# ESP32_Dev_Board.net
KiCad netlist of a schematic drawn in EasyEDA Pro
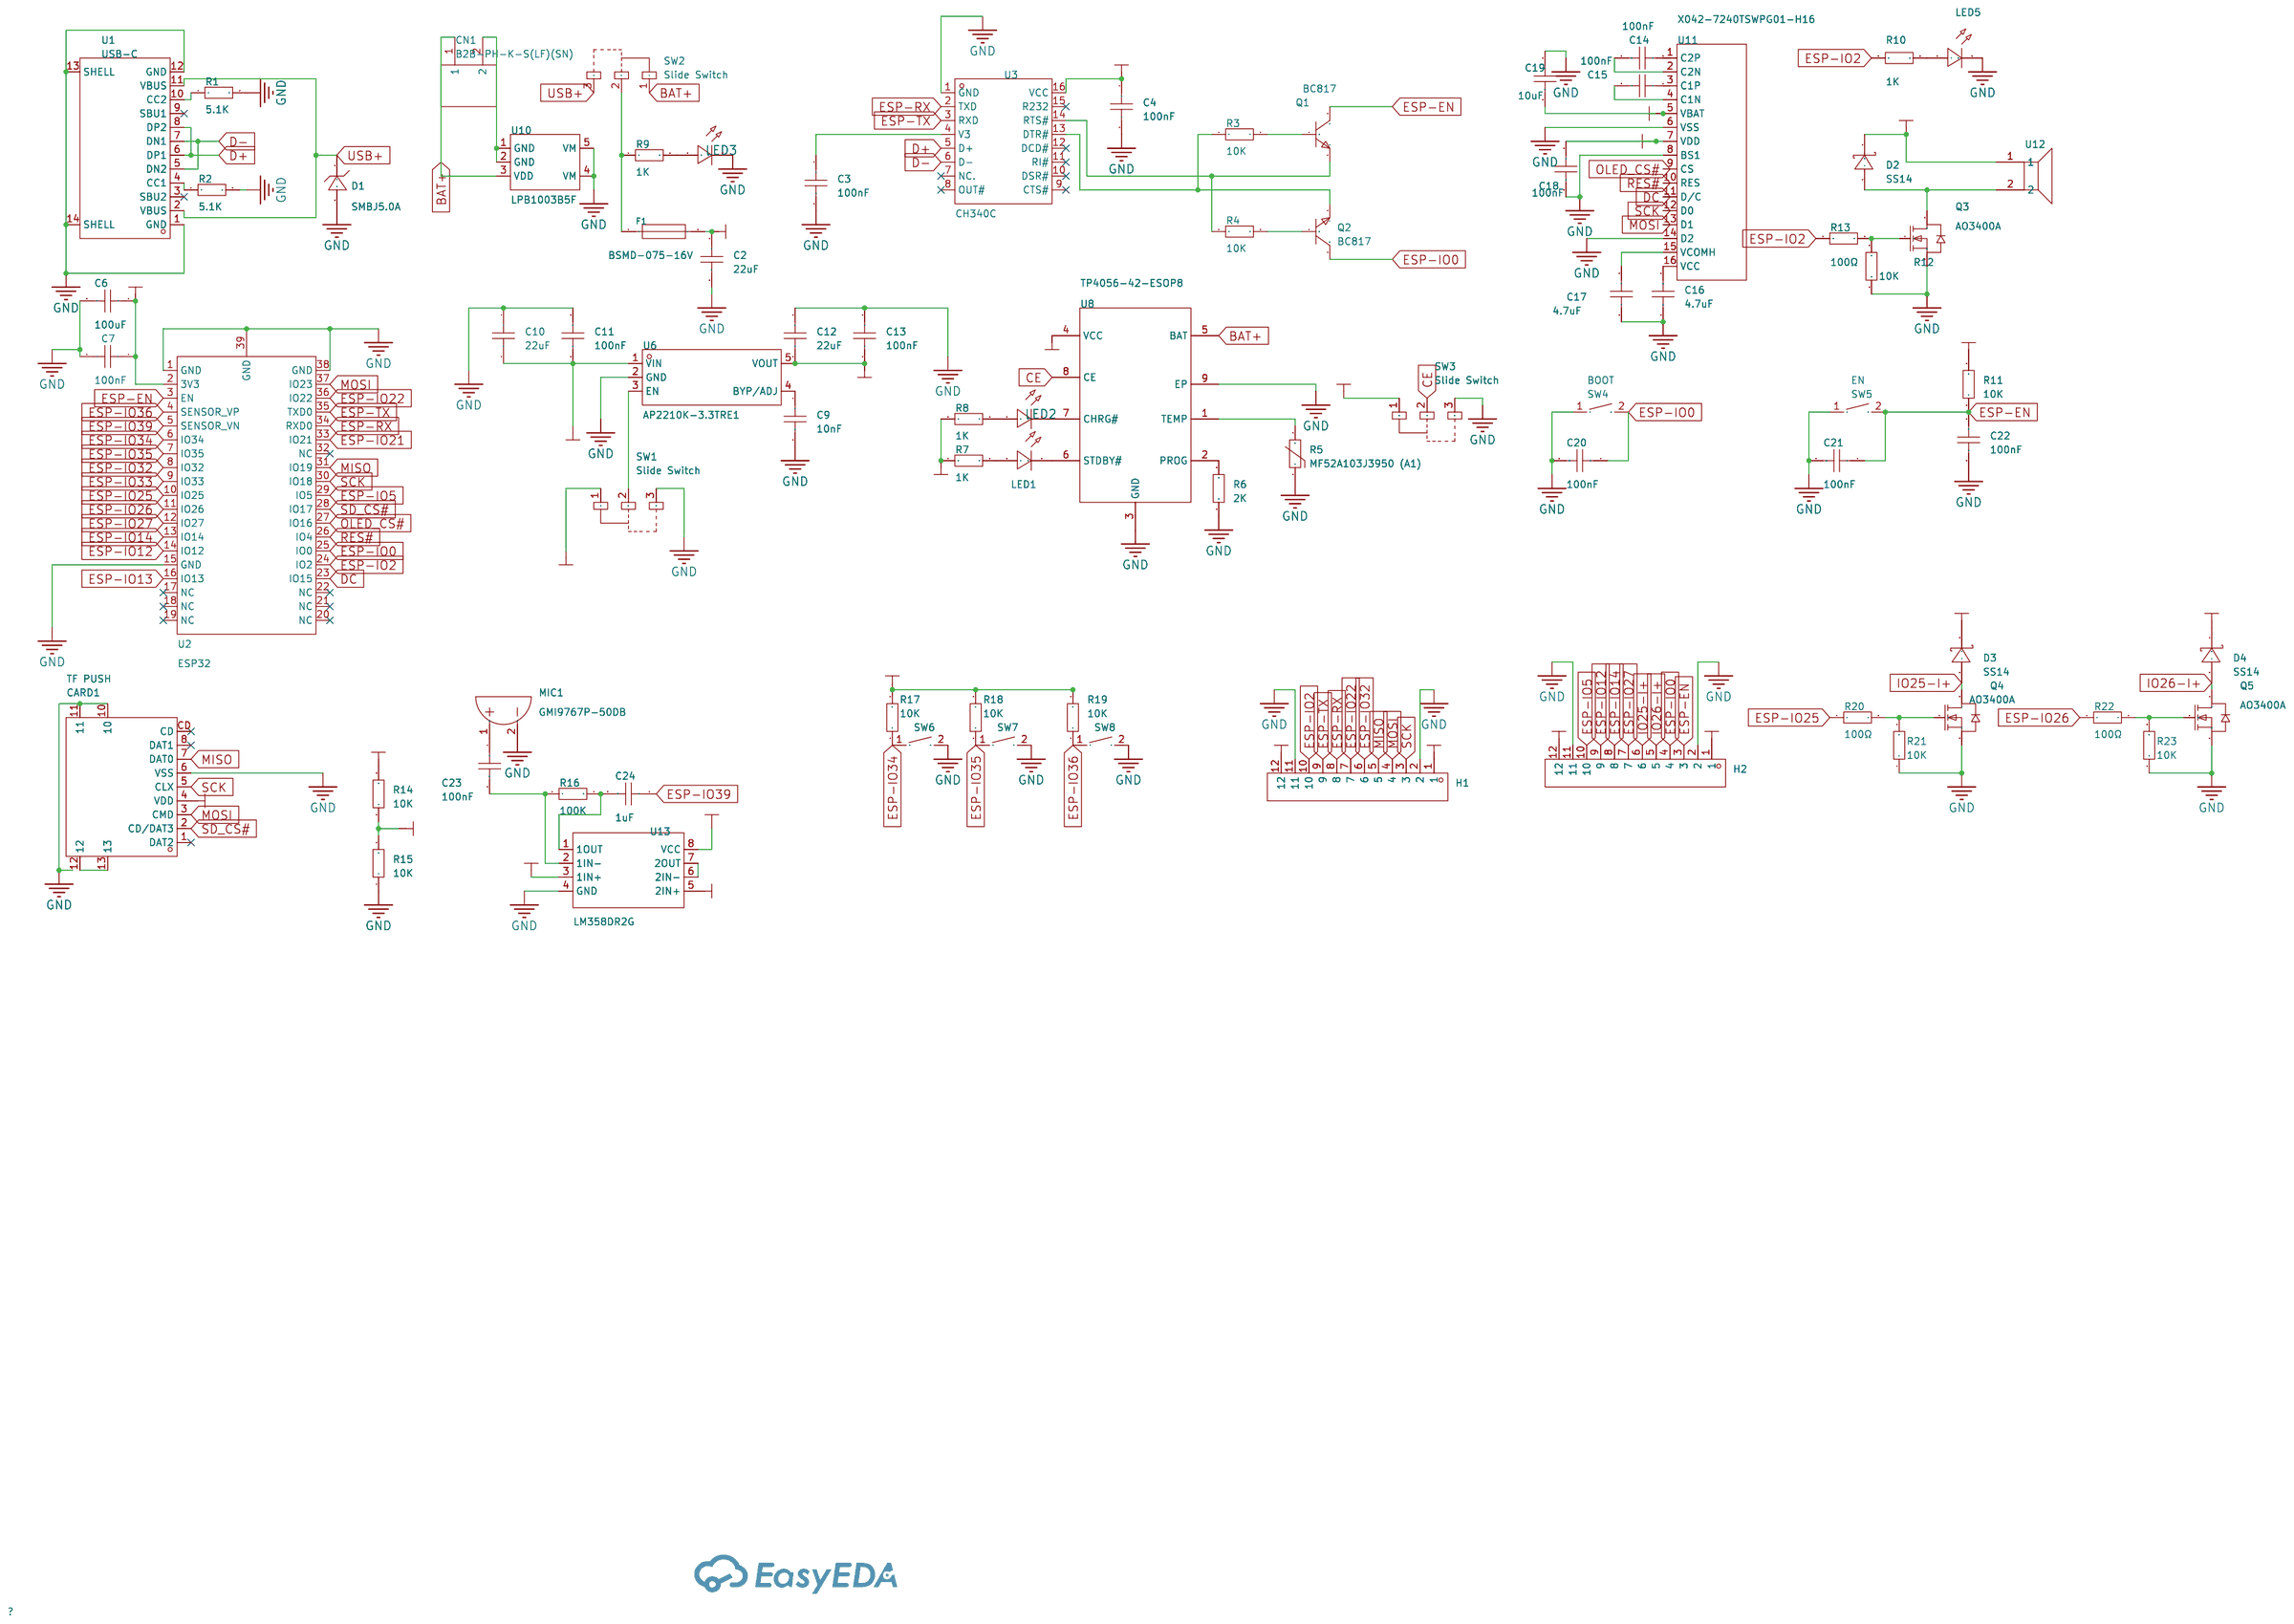
[diagram p0: schematic sheet]

(export (version "E")
  (design (tool "Eeschema 10.0.6"))
  (components
    (comp (ref "C2")
      (value "22uF")
      (footprint "easyedapro:C0201")
      (libsource (lib "easyedapro") (part "CAP"))
    )
    (comp (ref "C3")
      (value "100nF")
      (footprint "easyedapro:C0201")
      (libsource (lib "easyedapro") (part "CAP"))
    )
    (comp (ref "C4")
      (value "100nF")
      (footprint "easyedapro:C0201")
      (libsource (lib "easyedapro") (part "CAP"))
    )
    (comp (ref "C6")
      (value "100uF")
      (footprint "easyedapro:C0201")
      (libsource (lib "easyedapro") (part "CAP"))
    )
    (comp (ref "C7")
      (value "100nF")
      (footprint "easyedapro:C0201")
      (libsource (lib "easyedapro") (part "CAP"))
    )
    (comp (ref "C9")
      (value "10nF")
      (footprint "easyedapro:C0201")
      (libsource (lib "easyedapro") (part "CAP"))
    )
    (comp (ref "C10")
      (value "22uF")
      (footprint "easyedapro:C0201")
      (libsource (lib "easyedapro") (part "CAP"))
    )
    (comp (ref "C11")
      (value "100nF")
      (footprint "easyedapro:C0201")
      (libsource (lib "easyedapro") (part "CAP"))
    )
    (comp (ref "C12")
      (value "22uF")
      (footprint "easyedapro:C0201")
      (libsource (lib "easyedapro") (part "CAP"))
    )
    (comp (ref "C13")
      (value "100nF")
      (footprint "easyedapro:C0201")
      (libsource (lib "easyedapro") (part "CAP"))
    )
    (comp (ref "C14")
      (value "100nF")
      (footprint "easyedapro:C0201")
      (libsource (lib "easyedapro") (part "CAP"))
    )
    (comp (ref "C15")
      (value "100nF")
      (footprint "easyedapro:C0201")
      (libsource (lib "easyedapro") (part "CAP"))
    )
    (comp (ref "C16")
      (value "4.7uF")
      (footprint "easyedapro:C0201")
      (libsource (lib "easyedapro") (part "CAP"))
    )
    (comp (ref "C17")
      (value "4.7uF")
      (footprint "easyedapro:C0201")
      (libsource (lib "easyedapro") (part "CAP"))
    )
    (comp (ref "C18")
      (value "100nF")
      (footprint "easyedapro:C0201")
      (libsource (lib "easyedapro") (part "CAP"))
    )
    (comp (ref "C19")
      (value "10uF")
      (footprint "easyedapro:C0201")
      (libsource (lib "easyedapro") (part "CAP"))
    )
    (comp (ref "C20")
      (value "100nF")
      (footprint "easyedapro:C0201")
      (libsource (lib "easyedapro") (part "CAP"))
    )
    (comp (ref "C21")
      (value "100nF")
      (footprint "easyedapro:C0201")
      (libsource (lib "easyedapro") (part "CAP"))
    )
    (comp (ref "C22")
      (value "100nF")
      (footprint "easyedapro:C0201")
      (libsource (lib "easyedapro") (part "CAP"))
    )
    (comp (ref "C23")
      (value "100nF")
      (footprint "easyedapro:C0201")
      (libsource (lib "easyedapro") (part "CAP"))
    )
    (comp (ref "C24")
      (value "1uF")
      (footprint "easyedapro:C0201")
      (libsource (lib "easyedapro") (part "CAP"))
    )
    (comp (ref "CARD1")
      (value "TF PUSH")
      (footprint "easyedapro:TF-SMD_TF-PUSH")
      (fields (field (name "Manufacturer") "SHOU HAN(首韩)"))
      (libsource (lib "easyedapro") (part "TF PUSH"))
    )
    (comp (ref "CN1")
      (value "B2B-PH-K-S(LF)(SN)")
      (footprint "easyedapro:CONN-TH_B2B-PH-K-S")
      (fields (field (name "Manufacturer") "JST"))
      (libsource (lib "easyedapro") (part "B2B-PH-K-S(LF)(SN)"))
    )
    (comp (ref "D1")
      (value "SMBJ5.0A")
      (fields (field (name "Manufacturer") "Littelfuse(美国力特)"))
      (libsource (lib "easyedapro") (part "SMBJ5.0A_C83333"))
    )
    (comp (ref "D2")
      (value "SS14")
      (footprint "easyedapro:SMA_L4.4-W2.6-LS5.0-RD")
      (fields (field (name "Manufacturer") "HT(金誉)"))
      (libsource (lib "easyedapro") (part "SS14_C48782961"))
    )
    (comp (ref "D3")
      (value "SS14")
      (footprint "easyedapro:SMA_L4.4-W2.6-LS5.0-RD")
      (fields (field (name "Manufacturer") "HT(金誉)"))
      (libsource (lib "easyedapro") (part "SS14_C48782961"))
    )
    (comp (ref "D4")
      (value "SS14")
      (footprint "easyedapro:SMA_L4.4-W2.6-LS5.0-RD")
      (fields (field (name "Manufacturer") "HT(金誉)"))
      (libsource (lib "easyedapro") (part "SS14_C48782961"))
    )
    (comp (ref "F1")
      (value "BSMD-075-16V")
      (fields (field (name "Manufacturer") "BHFUSE(佰宏)"))
      (libsource (lib "easyedapro") (part "BSMD0805-075-16V"))
    )
    (comp (ref "H1")
      (value "~")
      (footprint "easyedapro:HDR-TH_12P-P2.54-V-M")
      (libsource (lib "easyedapro") (part "HDR_2.54-1x12P"))
    )
    (comp (ref "H2")
      (value "~")
      (footprint "easyedapro:HDR-TH_12P-P2.54-V-M")
      (libsource (lib "easyedapro") (part "HDR_2.54-1x12P"))
    )
    (comp (ref "LED1")
      (value "~")
      (footprint "easyedapro:LED0805-RD_GREEN")
      (libsource (lib "easyedapro") (part "LED_G"))
    )
    (comp (ref "LED2")
      (value "~")
      (footprint "easyedapro:LED0805-R-RD")
      (libsource (lib "easyedapro") (part "LED_R"))
    )
    (comp (ref "LED3")
      (value "~")
      (footprint "easyedapro:LED0805-R-RD")
      (libsource (lib "easyedapro") (part "LED_R"))
    )
    (comp (ref "LED5")
      (value "~")
      (footprint "easyedapro:LED0805-RD_GREEN")
      (libsource (lib "easyedapro") (part "LED_G"))
    )
    (comp (ref "MIC1")
      (value "GMI9767P-50DB")
      (footprint "easyedapro:MIC-TH_BD9.7-P2.54-D0.8-L-FD")
      (fields (field (name "Manufacturer") "INGHAi(赢海)"))
      (libsource (lib "easyedapro") (part "GMI9767P-50DB"))
    )
    (comp (ref "Q1")
      (value "BC817")
      (footprint "easyedapro:SOT-23-3_L2.9-W1.4-P1.91-LS2.6-BR")
      (fields (field (name "Manufacturer") "High Diode(海德)"))
      (libsource (lib "easyedapro") (part "BC817_C466643"))
    )
    (comp (ref "Q2")
      (value "BC817")
      (footprint "easyedapro:SOT-23-3_L2.9-W1.4-P1.91-LS2.6-BR")
      (fields (field (name "Manufacturer") "High Diode(海德)"))
      (libsource (lib "easyedapro") (part "BC817_C466643"))
    )
    (comp (ref "Q3")
      (value "AO3400A")
      (footprint "easyedapro:SOT-23-3_L2.9-W1.3-P1.90-LS2.4-BR")
      (fields (field (name "Manufacturer") "FUXINSEMI(富芯森美)"))
      (libsource (lib "easyedapro") (part "AO3400A_C5380685"))
    )
    (comp (ref "Q4")
      (value "AO3400A")
      (footprint "easyedapro:SOT-23-3_L2.9-W1.3-P1.90-LS2.4-BR")
      (fields (field (name "Manufacturer") "FUXINSEMI(富芯森美)"))
      (libsource (lib "easyedapro") (part "AO3400A_C5380685"))
    )
    (comp (ref "Q5")
      (value "AO3400A")
      (footprint "easyedapro:SOT-23-3_L2.9-W1.3-P1.90-LS2.4-BR")
      (fields (field (name "Manufacturer") "FUXINSEMI(富芯森美)"))
      (libsource (lib "easyedapro") (part "AO3400A_C5380685"))
    )
    (comp (ref "R1")
      (value "5.1K")
      (footprint "easyedapro:R0805")
      (libsource (lib "easyedapro") (part "Res"))
    )
    (comp (ref "R2")
      (value "5.1K")
      (footprint "easyedapro:R0805")
      (libsource (lib "easyedapro") (part "Res"))
    )
    (comp (ref "R3") (value "10K") (footprint "easyedapro:R0805") (libsource (lib "easyedapro") (part "Res")))
    (comp (ref "R4") (value "10K") (footprint "easyedapro:R0805") (libsource (lib "easyedapro") (part "Res")))
    (comp (ref "R5")
      (value "MF52A103J3950 (A1)")
      (footprint "easyedapro:RES-TH_L2.5-W2.5-P1.70-D0.3")
      (fields (field (name "Manufacturer") "时恒"))
      (libsource (lib "easyedapro") (part "10KΩ ±5%_C123378"))
    )
    (comp (ref "R6") (value "2K") (footprint "easyedapro:R0805") (libsource (lib "easyedapro") (part "Res")))
    (comp (ref "R7") (value "1K") (footprint "easyedapro:R0805") (libsource (lib "easyedapro") (part "Res")))
    (comp (ref "R8") (value "1K") (footprint "easyedapro:R0805") (libsource (lib "easyedapro") (part "Res")))
    (comp (ref "R9") (value "1K") (footprint "easyedapro:R0805") (libsource (lib "easyedapro") (part "Res")))
    (comp (ref "R10") (value "1K") (footprint "easyedapro:R0805") (libsource (lib "easyedapro") (part "Res")))
    (comp (ref "R11")
      (value "10K")
      (footprint "easyedapro:R0805")
      (libsource (lib "easyedapro") (part "Res"))
    )
    (comp (ref "R12")
      (value "10K")
      (footprint "easyedapro:R0805")
      (libsource (lib "easyedapro") (part "Res"))
    )
    (comp (ref "R13")
      (value "100Ω")
      (footprint "easyedapro:R0805")
      (libsource (lib "easyedapro") (part "Res"))
    )
    (comp (ref "R14")
      (value "10K")
      (footprint "easyedapro:R0805")
      (libsource (lib "easyedapro") (part "Res"))
    )
    (comp (ref "R15")
      (value "10K")
      (footprint "easyedapro:R0805")
      (libsource (lib "easyedapro") (part "Res"))
    )
    (comp (ref "R16")
      (value "100K")
      (footprint "easyedapro:R0805")
      (libsource (lib "easyedapro") (part "Res"))
    )
    (comp (ref "R17")
      (value "10K")
      (footprint "easyedapro:R0805")
      (libsource (lib "easyedapro") (part "Res"))
    )
    (comp (ref "R18")
      (value "10K")
      (footprint "easyedapro:R0805")
      (libsource (lib "easyedapro") (part "Res"))
    )
    (comp (ref "R19")
      (value "10K")
      (footprint "easyedapro:R0805")
      (libsource (lib "easyedapro") (part "Res"))
    )
    (comp (ref "R20")
      (value "100Ω")
      (footprint "easyedapro:R0805")
      (libsource (lib "easyedapro") (part "Res"))
    )
    (comp (ref "R21")
      (value "10K")
      (footprint "easyedapro:R0805")
      (libsource (lib "easyedapro") (part "Res"))
    )
    (comp (ref "R22")
      (value "100Ω")
      (footprint "easyedapro:R0805")
      (libsource (lib "easyedapro") (part "Res"))
    )
    (comp (ref "R23")
      (value "10K")
      (footprint "easyedapro:R0805")
      (libsource (lib "easyedapro") (part "Res"))
    )
    (comp (ref "SW1")
      (value "Slide Switch")
      (footprint "easyedapro:SW-SMD_3P-L9.1-W3.5-P2.50_MST-12D18G2")
      (fields (field (name "Manufacturer") "SHOU HAN(首韩)"))
      (libsource (lib "easyedapro") (part "MST-12D18G2 SMD SLIDE SWITCH"))
    )
    (comp (ref "SW2")
      (value "Slide Switch")
      (footprint "easyedapro:SW-SMD_3P-L9.1-W3.5-P2.50_MST-12D18G2")
      (fields (field (name "Manufacturer") "SHOU HAN(首韩)"))
      (libsource (lib "easyedapro") (part "MST-12D18G2 SMD SLIDE SWITCH"))
    )
    (comp (ref "SW3")
      (value "Slide Switch")
      (footprint "easyedapro:SW-SMD_3P-L9.1-W3.5-P2.50_MST-12D18G2")
      (fields (field (name "Manufacturer") "SHOU HAN(首韩)"))
      (libsource (lib "easyedapro") (part "MST-12D18G2 SMD SLIDE SWITCH"))
    )
    (comp (ref "SW4")
      (value "BOOT")
      (footprint "easyedapro:KEY-SMD_L4.0-W3.0-LS4.9-1")
      (fields (field (name "Manufacturer") "hanxia(韩下)"))
      (libsource (lib "easyedapro") (part "HX 3X4X2-2P-1.6N TACTILE SWITCH"))
    )
    (comp (ref "SW5")
      (value "EN")
      (footprint "easyedapro:KEY-SMD_L4.0-W3.0-LS4.9-1")
      (fields (field (name "Manufacturer") "hanxia(韩下)"))
      (libsource (lib "easyedapro") (part "HX 3X4X2-2P-1.6N TACTILE SWITCH"))
    )
    (comp (ref "SW6")
      (value "EN")
      (footprint "easyedapro:KEY-SMD_L4.0-W3.0-LS4.9-1")
      (fields (field (name "Manufacturer") "hanxia(韩下)"))
      (libsource (lib "easyedapro") (part "HX 3X4X2-2P-1.6N TACTILE SWITCH"))
    )
    (comp (ref "SW7")
      (value "EN")
      (footprint "easyedapro:KEY-SMD_L4.0-W3.0-LS4.9-1")
      (fields (field (name "Manufacturer") "hanxia(韩下)"))
      (libsource (lib "easyedapro") (part "HX 3X4X2-2P-1.6N TACTILE SWITCH"))
    )
    (comp (ref "SW8")
      (value "EN")
      (footprint "easyedapro:KEY-SMD_L4.0-W3.0-LS4.9-1")
      (fields (field (name "Manufacturer") "hanxia(韩下)"))
      (libsource (lib "easyedapro") (part "HX 3X4X2-2P-1.6N TACTILE SWITCH"))
    )
    (comp (ref "U1")
      (value "USB-C")
      (footprint "easyedapro:USB-C-SMD_TYPE-C-6PIN-2MD-073")
      (fields (field (name "Manufacturer") "SHOU HAN(首韩)"))
      (libsource (lib "easyedapro") (part "TYPE-C 16PIN 2MD(073)"))
    )
    (comp (ref "U2")
      (value "ESP32")
      (footprint "easyedapro:WIFI-SMD_ESP32-WROOM-32E")
      (fields
        (field (name "Manufacturer Part") "ESP32-WROOM-32E-N4")
        (field (name "Manufacturer") "ESPRESSIF(乐鑫)")
      )
      (libsource (lib "easyedapro") (part "ESP32-WROOM-32E(4MB)"))
    )
    (comp (ref "U3")
      (value "CH340C")
      (footprint "easyedapro:SOP-16_L10.0-W3.9-P1.27-LS6.0-BL")
      (fields (field (name "Manufacturer") "WCH(南京沁恒)"))
      (libsource (lib "easyedapro") (part "CH340C"))
    )
    (comp (ref "U6")
      (value "AP2210K-3.3TRE1")
      (footprint "easyedapro:SOT-23-5_L3.0-W1.7-P0.95-LS2.8-BR")
      (fields (field (name "Manufacturer") "DIODES(美台)"))
      (libsource (lib "easyedapro") (part "AP2210K-3.3TRE1"))
    )
    (comp (ref "U8")
      (value "TP4056-42-ESOP8")
      (footprint "easyedapro:ESOP-8_L4.9-W3.9-P1.27-LS6.0-BL-EP")
      (fields (field (name "Manufacturer") "TOPPOWER(南京拓微)"))
      (libsource (lib "easyedapro") (part "TP4056"))
    )
    (comp (ref "U10")
      (value "LPB1003B5F")
      (footprint "easyedapro:SOT-23-5_L3.0-W1.6-P0.95-LS2.8-BL")
      (fields (field (name "Manufacturer") "LOWPOWER(微源半导体)"))
      (libsource (lib "easyedapro") (part "LPB1003B5F"))
    )
    (comp (ref "U11")
      (value "X042-7240TSWPG01-H16")
      (footprint "easyedapro:OLED-SMD_16P-P0.65-X042-7240TSWPG01-H16")
      (fields (field (name "Manufacturer") "Wisevision(新智景)"))
      (libsource (lib "easyedapro") (part "X042-7240TSWPG01-H16_C18723008"))
    )
    (comp (ref "U12") (value "~") (description "C18221550") (libsource (lib "easyedapro") (part "Speaker")))
    (comp (ref "U13")
      (value "LM358DR2G")
      (footprint "easyedapro:SOIC-8_L5.0-W4.0-P1.27-LS6.0-BL")
      (fields (field (name "Manufacturer") "onsemi(安森美)"))
      (libsource (lib "easyedapro") (part "LM358DR2G"))
    )
  )
  (nets
    (net (code "1") (name "+1.65V") (class "Default")
      (node (ref "R14") (pin "1") (pinfunction "1_1") (pintype "input"))
      (node (ref "R15") (pin "2") (pinfunction "2_2") (pintype "input"))
      (node (ref "U13") (pin "3") (pinfunction "1IN+_3") (pintype "unspecified"))
      (node (ref "U13") (pin "5") (pinfunction "2IN+_5") (pintype "unspecified"))
    )
    (net (code "2") (name "+3V3") (class "Default")
      (node (ref "C12") (pin "2") (pinfunction "2_2") (pintype "input"))
      (node (ref "C13") (pin "2") (pinfunction "2_2") (pintype "input"))
      (node (ref "C18") (pin "1") (pinfunction "1_1") (pintype "input"))
      (node (ref "C19") (pin "2") (pinfunction "2_2") (pintype "input"))
      (node (ref "C6") (pin "1") (pinfunction "1_1") (pintype "input"))
      (node (ref "C7") (pin "1") (pinfunction "1_1") (pintype "input"))
      (node (ref "CARD1") (pin "4") (pinfunction "VDD_4") (pintype "unspecified"))
      (node (ref "H1") (pin "1") (pinfunction "1_1") (pintype "input"))
      (node (ref "H2") (pin "12") (pinfunction "12_12") (pintype "input"))
      (node (ref "R11") (pin "2") (pinfunction "2_2") (pintype "input"))
      (node (ref "R14") (pin "2") (pinfunction "2_2") (pintype "input"))
      (node (ref "R17") (pin "2") (pinfunction "2_2") (pintype "input"))
      (node (ref "R18") (pin "2") (pinfunction "2_2") (pintype "input"))
      (node (ref "R19") (pin "2") (pinfunction "2_2") (pintype "input"))
      (node (ref "U11") (pin "5") (pinfunction "VBAT_5") (pintype "unspecified"))
      (node (ref "U11") (pin "7") (pinfunction "VDD_7") (pintype "unspecified"))
      (node (ref "U13") (pin "8") (pinfunction "VCC_8") (pintype "unspecified"))
      (node (ref "U2") (pin "2") (pinfunction "3V3_2") (pintype "unspecified"))
      (node (ref "U6") (pin "5") (pinfunction "VOUT_5") (pintype "input"))
    )
    (net (code "3") (name "BAT+") (class "Default")
      (node (ref "CN1") (pin "1") (pinfunction "1_1") (pintype "input"))
      (node (ref "SW2") (pin "1") (pinfunction "1_1") (pintype "unspecified"))
      (node (ref "U10") (pin "3") (pinfunction "VDD_3") (pintype "unspecified"))
      (node (ref "U8") (pin "5") (pinfunction "BAT_5") (pintype "unspecified"))
    )
    (net (code "4") (name "CE") (class "Default")
      (node (ref "SW3") (pin "2") (pinfunction "2_2") (pintype "unspecified"))
      (node (ref "U8") (pin "8") (pinfunction "CE_8") (pintype "unspecified"))
    )
    (net (code "5") (name "D+") (class "Default")
      (node (ref "U1") (pin "6") (pinfunction "DP1_6") (pintype "unspecified"))
      (node (ref "U1") (pin "8") (pinfunction "DP2_8") (pintype "unspecified"))
      (node (ref "U3") (pin "5") (pinfunction "D+_5") (pintype "unspecified"))
    )
    (net (code "6") (name "D-") (class "Default")
      (node (ref "U1") (pin "5") (pinfunction "DN2_5") (pintype "unspecified"))
      (node (ref "U1") (pin "7") (pinfunction "DN1_7") (pintype "unspecified"))
      (node (ref "U3") (pin "6") (pinfunction "D-_6") (pintype "unspecified"))
    )
    (net (code "7") (name "DC") (class "Default")
      (node (ref "U11") (pin "11") (pinfunction "D/C_11") (pintype "unspecified"))
      (node (ref "U2") (pin "23") (pinfunction "IO15_23") (pintype "unspecified"))
    )
    (net (code "8") (name "ESP-EN") (class "Default")
      (node (ref "C21") (pin "1") (pinfunction "1_1") (pintype "input"))
      (node (ref "C22") (pin "1") (pinfunction "1_1") (pintype "input"))
      (node (ref "H2") (pin "3") (pinfunction "3_3") (pintype "input"))
      (node (ref "Q1") (pin "3") (pinfunction "C_3") (pintype "unspecified"))
      (node (ref "R11") (pin "1") (pinfunction "1_1") (pintype "input"))
      (node (ref "SW5") (pin "2") (pinfunction "2_2") (pintype "unspecified"))
      (node (ref "U2") (pin "3") (pinfunction "EN_3") (pintype "unspecified"))
    )
    (net (code "9") (name "ESP-IO0") (class "Default")
      (node (ref "C20") (pin "1") (pinfunction "1_1") (pintype "input"))
      (node (ref "H2") (pin "4") (pinfunction "4_4") (pintype "input"))
      (node (ref "Q2") (pin "3") (pinfunction "C_3") (pintype "unspecified"))
      (node (ref "SW4") (pin "2") (pinfunction "2_2") (pintype "unspecified"))
      (node (ref "U2") (pin "25") (pinfunction "IO0_25") (pintype "unspecified"))
    )
    (net (code "10") (name "ESP-IO2") (class "Default")
      (node (ref "H1") (pin "10") (pinfunction "10_10") (pintype "input"))
      (node (ref "R10") (pin "1") (pinfunction "1_1") (pintype "input"))
      (node (ref "R13") (pin "1") (pinfunction "1_1") (pintype "input"))
      (node (ref "U2") (pin "24") (pinfunction "IO2_24") (pintype "unspecified"))
    )
    (net (code "11") (name "ESP-IO5") (class "Default")
      (node (ref "H2") (pin "10") (pinfunction "10_10") (pintype "input"))
      (node (ref "U2") (pin "29") (pinfunction "IO5_29") (pintype "unspecified"))
    )
    (net (code "12") (name "ESP-IO12") (class "Default")
      (node (ref "H2") (pin "9") (pinfunction "9_9") (pintype "input"))
      (node (ref "U2") (pin "14") (pinfunction "IO12_14") (pintype "unspecified"))
    )
    (net (code "13") (name "ESP-IO13") (class "Default")
      (node (ref "U2") (pin "16") (pinfunction "IO13_16") (pintype "unspecified"))
    )
    (net (code "14") (name "ESP-IO14") (class "Default")
      (node (ref "H2") (pin "8") (pinfunction "8_8") (pintype "input"))
      (node (ref "U2") (pin "13") (pinfunction "IO14_13") (pintype "unspecified"))
    )
    (net (code "15") (name "ESP-IO21") (class "Default")
      (node (ref "U2") (pin "33") (pinfunction "IO21_33") (pintype "unspecified"))
    )
    (net (code "16") (name "ESP-IO22") (class "Default")
      (node (ref "H1") (pin "7") (pinfunction "7_7") (pintype "input"))
      (node (ref "U2") (pin "36") (pinfunction "IO22_36") (pintype "unspecified"))
    )
    (net (code "17") (name "ESP-IO25") (class "Default")
      (node (ref "R20") (pin "1") (pinfunction "1_1") (pintype "input"))
      (node (ref "U2") (pin "10") (pinfunction "IO25_10") (pintype "unspecified"))
    )
    (net (code "18") (name "ESP-IO26") (class "Default")
      (node (ref "R22") (pin "1") (pinfunction "1_1") (pintype "input"))
      (node (ref "U2") (pin "11") (pinfunction "IO26_11") (pintype "unspecified"))
    )
    (net (code "19") (name "ESP-IO27") (class "Default")
      (node (ref "H2") (pin "7") (pinfunction "7_7") (pintype "input"))
      (node (ref "U2") (pin "12") (pinfunction "IO27_12") (pintype "unspecified"))
    )
    (net (code "20") (name "ESP-IO32") (class "Default")
      (node (ref "H1") (pin "6") (pinfunction "6_6") (pintype "input"))
      (node (ref "U2") (pin "8") (pinfunction "IO32_8") (pintype "unspecified"))
    )
    (net (code "21") (name "ESP-IO33") (class "Default")
      (node (ref "U2") (pin "9") (pinfunction "IO33_9") (pintype "unspecified"))
    )
    (net (code "22") (name "ESP-IO34") (class "Default")
      (node (ref "R17") (pin "1") (pinfunction "1_1") (pintype "input"))
      (node (ref "SW6") (pin "1") (pinfunction "1_1") (pintype "unspecified"))
      (node (ref "U2") (pin "6") (pinfunction "IO34_6") (pintype "unspecified"))
    )
    (net (code "23") (name "ESP-IO35") (class "Default")
      (node (ref "R18") (pin "1") (pinfunction "1_1") (pintype "input"))
      (node (ref "SW7") (pin "1") (pinfunction "1_1") (pintype "unspecified"))
      (node (ref "U2") (pin "7") (pinfunction "IO35_7") (pintype "unspecified"))
    )
    (net (code "24") (name "ESP-IO36") (class "Default")
      (node (ref "R19") (pin "1") (pinfunction "1_1") (pintype "input"))
      (node (ref "SW8") (pin "1") (pinfunction "1_1") (pintype "unspecified"))
      (node (ref "U2") (pin "4") (pinfunction "SENSOR_VP_4") (pintype "unspecified"))
    )
    (net (code "25") (name "ESP-IO39") (class "Default")
      (node (ref "C24") (pin "1") (pinfunction "1_1") (pintype "input"))
      (node (ref "U2") (pin "5") (pinfunction "SENSOR_VN_5") (pintype "unspecified"))
    )
    (net (code "26") (name "ESP-RX") (class "Default")
      (node (ref "H1") (pin "8") (pinfunction "8_8") (pintype "input"))
      (node (ref "U2") (pin "34") (pinfunction "RXD0_34") (pintype "unspecified"))
      (node (ref "U3") (pin "2") (pinfunction "TXD_2") (pintype "unspecified"))
    )
    (net (code "27") (name "ESP-TX") (class "Default")
      (node (ref "H1") (pin "9") (pinfunction "9_9") (pintype "input"))
      (node (ref "U2") (pin "35") (pinfunction "TXD0_35") (pintype "unspecified"))
      (node (ref "U3") (pin "3") (pinfunction "RXD_3") (pintype "unspecified"))
    )
    (net (code "28") (name "GND") (class "Default")
      (node (ref "C10") (pin "1") (pinfunction "1_1") (pintype "input"))
      (node (ref "C11") (pin "1") (pinfunction "1_1") (pintype "input"))
      (node (ref "C12") (pin "1") (pinfunction "1_1") (pintype "input"))
      (node (ref "C13") (pin "1") (pinfunction "1_1") (pintype "input"))
      (node (ref "C16") (pin "2") (pinfunction "2_2") (pintype "input"))
      (node (ref "C17") (pin "2") (pinfunction "2_2") (pintype "input"))
      (node (ref "C18") (pin "2") (pinfunction "2_2") (pintype "input"))
      (node (ref "C19") (pin "1") (pinfunction "1_1") (pintype "input"))
      (node (ref "C2") (pin "2") (pinfunction "2_2") (pintype "input"))
      (node (ref "C20") (pin "2") (pinfunction "2_2") (pintype "input"))
      (node (ref "C21") (pin "2") (pinfunction "2_2") (pintype "input"))
      (node (ref "C22") (pin "2") (pinfunction "2_2") (pintype "input"))
      (node (ref "C3") (pin "2") (pinfunction "2_2") (pintype "input"))
      (node (ref "C4") (pin "2") (pinfunction "2_2") (pintype "input"))
      (node (ref "C6") (pin "2") (pinfunction "2_2") (pintype "input"))
      (node (ref "C7") (pin "2") (pinfunction "2_2") (pintype "input"))
      (node (ref "C9") (pin "2") (pinfunction "2_2") (pintype "input"))
      (node (ref "CARD1") (pin "10") (pinfunction "10_10") (pintype "unspecified"))
      (node (ref "CARD1") (pin "11") (pinfunction "11_11") (pintype "unspecified"))
      (node (ref "CARD1") (pin "6") (pinfunction "VSS_6") (pintype "unspecified"))
      (node (ref "D1") (pin "2") (pinfunction "2_2") (pintype "unspecified"))
      (node (ref "H1") (pin "11") (pinfunction "11_11") (pintype "input"))
      (node (ref "H1") (pin "2") (pinfunction "2_2") (pintype "input"))
      (node (ref "H2") (pin "11") (pinfunction "11_11") (pintype "input"))
      (node (ref "H2") (pin "2") (pinfunction "2_2") (pintype "input"))
      (node (ref "LED3") (pin "2") (pinfunction "C_2") (pintype "input"))
      (node (ref "LED5") (pin "1") (pinfunction "C_1") (pintype "input"))
      (node (ref "MIC1") (pin "2") (pinfunction "2_2") (pintype "unspecified"))
      (node (ref "Q3") (pin "2") (pinfunction "S_2") (pintype "unspecified"))
      (node (ref "Q4") (pin "2") (pinfunction "S_2") (pintype "unspecified"))
      (node (ref "Q5") (pin "2") (pinfunction "S_2") (pintype "unspecified"))
      (node (ref "R1") (pin "2") (pinfunction "2_2") (pintype "input"))
      (node (ref "R12") (pin "1") (pinfunction "1_1") (pintype "input"))
      (node (ref "R15") (pin "1") (pinfunction "1_1") (pintype "input"))
      (node (ref "R2") (pin "2") (pinfunction "2_2") (pintype "input"))
      (node (ref "R21") (pin "1") (pinfunction "1_1") (pintype "input"))
      (node (ref "R23") (pin "1") (pinfunction "1_1") (pintype "input"))
      (node (ref "R5") (pin "1") (pinfunction "1_1") (pintype "unspecified"))
      (node (ref "R6") (pin "1") (pinfunction "1_1") (pintype "input"))
      (node (ref "SW1") (pin "3") (pinfunction "3_3") (pintype "unspecified"))
      (node (ref "SW3") (pin "3") (pinfunction "3_3") (pintype "unspecified"))
      (node (ref "SW4") (pin "1") (pinfunction "1_1") (pintype "unspecified"))
      (node (ref "SW5") (pin "1") (pinfunction "1_1") (pintype "unspecified"))
      (node (ref "SW6") (pin "2") (pinfunction "2_2") (pintype "unspecified"))
      (node (ref "SW7") (pin "2") (pinfunction "2_2") (pintype "unspecified"))
      (node (ref "SW8") (pin "2") (pinfunction "2_2") (pintype "unspecified"))
      (node (ref "U1") (pin "1") (pinfunction "GND_1") (pintype "unspecified"))
      (node (ref "U1") (pin "12") (pinfunction "GND_12") (pintype "unspecified"))
      (node (ref "U1") (pin "13") (pinfunction "SHELL_13") (pintype "unspecified"))
      (node (ref "U1") (pin "14") (pinfunction "SHELL_14") (pintype "unspecified"))
      (node (ref "U10") (pin "4") (pinfunction "VM_4") (pintype "unspecified"))
      (node (ref "U10") (pin "5") (pinfunction "VM_5") (pintype "unspecified"))
      (node (ref "U11") (pin "14") (pinfunction "D2_14") (pintype "unspecified"))
      (node (ref "U11") (pin "6") (pinfunction "VSS_6") (pintype "unspecified"))
      (node (ref "U11") (pin "8") (pinfunction "BS1_8") (pintype "unspecified"))
      (node (ref "U13") (pin "4") (pinfunction "GND_4") (pintype "unspecified"))
      (node (ref "U2") (pin "1") (pinfunction "GND_1") (pintype "unspecified"))
      (node (ref "U2") (pin "15") (pinfunction "GND_15") (pintype "unspecified"))
      (node (ref "U2") (pin "38") (pinfunction "GND_38") (pintype "unspecified"))
      (node (ref "U2") (pin "39") (pinfunction "GND_39") (pintype "unspecified"))
      (node (ref "U3") (pin "1") (pinfunction "GND_1") (pintype "unspecified"))
      (node (ref "U6") (pin "2") (pinfunction "GND_2") (pintype "input"))
      (node (ref "U8") (pin "3") (pinfunction "GND_3") (pintype "unspecified"))
      (node (ref "U8") (pin "9") (pinfunction "EP_9") (pintype "unspecified"))
    )
    (net (code "29") (name "IO25-I+") (class "Default")
      (node (ref "D3") (pin "2") (pinfunction "A_2") (pintype "unspecified"))
      (node (ref "H2") (pin "6") (pinfunction "6_6") (pintype "input"))
      (node (ref "Q4") (pin "3") (pinfunction "D_3") (pintype "unspecified"))
    )
    (net (code "30") (name "IO26-I+") (class "Default")
      (node (ref "D4") (pin "2") (pinfunction "A_2") (pintype "unspecified"))
      (node (ref "H2") (pin "5") (pinfunction "5_5") (pintype "input"))
      (node (ref "Q5") (pin "3") (pinfunction "D_3") (pintype "unspecified"))
    )
    (net (code "31") (name "MISO") (class "Default")
      (node (ref "CARD1") (pin "7") (pinfunction "DAT0_7") (pintype "unspecified"))
      (node (ref "H1") (pin "5") (pinfunction "5_5") (pintype "input"))
      (node (ref "U2") (pin "31") (pinfunction "IO19_31") (pintype "unspecified"))
    )
    (net (code "32") (name "MOSI") (class "Default")
      (node (ref "CARD1") (pin "3") (pinfunction "CMD_3") (pintype "unspecified"))
      (node (ref "H1") (pin "4") (pinfunction "4_4") (pintype "input"))
      (node (ref "U11") (pin "13") (pinfunction "D1_13") (pintype "unspecified"))
      (node (ref "U2") (pin "37") (pinfunction "IO23_37") (pintype "unspecified"))
    )
    (net (code "33") (name "Net-(C23-Pad1)") (class "Default")
      (node (ref "C23") (pin "1") (pinfunction "1_1") (pintype "input"))
      (node (ref "MIC1") (pin "1") (pinfunction "1_1") (pintype "unspecified"))
    )
    (net (code "34") (name "Net-(CARD1-Pad12)") (class "Default")
      (node (ref "CARD1") (pin "12") (pinfunction "12_12") (pintype "unspecified"))
      (node (ref "CARD1") (pin "13") (pinfunction "13_13") (pintype "unspecified"))
    )
    (net (code "35") (name "Net-(CN1-Pad2)") (class "Default")
      (node (ref "CN1") (pin "2") (pinfunction "2_2") (pintype "input"))
      (node (ref "U10") (pin "1") (pinfunction "GND_1") (pintype "unspecified"))
      (node (ref "U10") (pin "2") (pinfunction "GND_2") (pintype "unspecified"))
    )
    (net (code "36") (name "Net-(D2-A)") (class "Default")
      (node (ref "D2") (pin "2") (pinfunction "A_2") (pintype "unspecified"))
      (node (ref "Q3") (pin "3") (pinfunction "D_3") (pintype "unspecified"))
      (node (ref "U12") (pin "2") (pinfunction "2_2") (pintype "input"))
    )
    (net (code "37") (name "Net-(F1-Pad1)") (class "Default")
      (node (ref "F1") (pin "1") (pinfunction "1_1") (pintype "input"))
      (node (ref "R9") (pin "1") (pinfunction "1_1") (pintype "input"))
      (node (ref "SW2") (pin "2") (pinfunction "2_2") (pintype "unspecified"))
    )
    (net (code "38") (name "Net-(LED1-A)") (class "Default")
      (node (ref "LED1") (pin "2") (pinfunction "A_2") (pintype "input"))
      (node (ref "R7") (pin "2") (pinfunction "2_2") (pintype "input"))
    )
    (net (code "39") (name "Net-(LED1-C)") (class "Default")
      (node (ref "LED1") (pin "1") (pinfunction "C_1") (pintype "input"))
      (node (ref "U8") (pin "6") (pinfunction "STDBY#_6") (pintype "unspecified"))
    )
    (net (code "40") (name "Net-(LED2-A)") (class "Default")
      (node (ref "LED2") (pin "1") (pinfunction "A_1") (pintype "input"))
      (node (ref "R8") (pin "2") (pinfunction "2_2") (pintype "input"))
    )
    (net (code "41") (name "Net-(LED2-C)") (class "Default")
      (node (ref "LED2") (pin "2") (pinfunction "C_2") (pintype "input"))
      (node (ref "U8") (pin "7") (pinfunction "CHRG#_7") (pintype "unspecified"))
    )
    (net (code "42") (name "Net-(LED3-A)") (class "Default")
      (node (ref "LED3") (pin "1") (pinfunction "A_1") (pintype "input"))
      (node (ref "R9") (pin "2") (pinfunction "2_2") (pintype "input"))
    )
    (net (code "43") (name "Net-(LED5-A)") (class "Default")
      (node (ref "LED5") (pin "2") (pinfunction "A_2") (pintype "input"))
      (node (ref "R10") (pin "2") (pinfunction "2_2") (pintype "input"))
    )
    (net (code "44") (name "Net-(Q1-B)") (class "Default")
      (node (ref "Q1") (pin "1") (pinfunction "B_1") (pintype "unspecified"))
      (node (ref "R3") (pin "2") (pinfunction "2_2") (pintype "input"))
    )
    (net (code "45") (name "Net-(Q1-E)") (class "Default")
      (node (ref "Q1") (pin "2") (pinfunction "E_2") (pintype "unspecified"))
      (node (ref "R4") (pin "1") (pinfunction "1_1") (pintype "input"))
      (node (ref "U3") (pin "14") (pinfunction "RTS#_14") (pintype "unspecified"))
    )
    (net (code "46") (name "Net-(Q2-B)") (class "Default")
      (node (ref "Q2") (pin "1") (pinfunction "B_1") (pintype "unspecified"))
      (node (ref "R4") (pin "2") (pinfunction "2_2") (pintype "input"))
    )
    (net (code "47") (name "Net-(Q2-E)") (class "Default")
      (node (ref "Q2") (pin "2") (pinfunction "E_2") (pintype "unspecified"))
      (node (ref "R3") (pin "1") (pinfunction "1_1") (pintype "input"))
      (node (ref "U3") (pin "13") (pinfunction "DTR#_13") (pintype "unspecified"))
    )
    (net (code "48") (name "Net-(Q3-G)") (class "Default")
      (node (ref "Q3") (pin "1") (pinfunction "G_1") (pintype "unspecified"))
      (node (ref "R12") (pin "2") (pinfunction "2_2") (pintype "input"))
      (node (ref "R13") (pin "2") (pinfunction "2_2") (pintype "input"))
    )
    (net (code "49") (name "Net-(Q4-G)") (class "Default")
      (node (ref "Q4") (pin "1") (pinfunction "G_1") (pintype "unspecified"))
      (node (ref "R20") (pin "2") (pinfunction "2_2") (pintype "input"))
      (node (ref "R21") (pin "2") (pinfunction "2_2") (pintype "input"))
    )
    (net (code "50") (name "Net-(Q5-G)") (class "Default")
      (node (ref "Q5") (pin "1") (pinfunction "G_1") (pintype "unspecified"))
      (node (ref "R22") (pin "2") (pinfunction "2_2") (pintype "input"))
      (node (ref "R23") (pin "2") (pinfunction "2_2") (pintype "input"))
    )
    (net (code "51") (name "Net-(U1-CC1)") (class "Default")
      (node (ref "R2") (pin "1") (pinfunction "1_1") (pintype "input"))
      (node (ref "U1") (pin "4") (pinfunction "CC1_4") (pintype "unspecified"))
    )
    (net (code "52") (name "Net-(U1-CC2)") (class "Default")
      (node (ref "R1") (pin "1") (pinfunction "1_1") (pintype "input"))
      (node (ref "U1") (pin "10") (pinfunction "CC2_10") (pintype "unspecified"))
    )
    (net (code "53") (name "Net-(U3-V3)") (class "Default")
      (node (ref "C3") (pin "1") (pinfunction "1_1") (pintype "input"))
      (node (ref "U3") (pin "4") (pinfunction "V3_4") (pintype "unspecified"))
    )
    (net (code "54") (name "Net-(U6-BYP{slash}ADJ)") (class "Default")
      (node (ref "C9") (pin "1") (pinfunction "1_1") (pintype "input"))
      (node (ref "U6") (pin "4") (pinfunction "BYP/ADJ_4") (pintype "input"))
    )
    (net (code "55") (name "Net-(U6-EN)") (class "Default")
      (node (ref "SW1") (pin "2") (pinfunction "2_2") (pintype "unspecified"))
      (node (ref "U6") (pin "3") (pinfunction "EN_3") (pintype "input"))
    )
    (net (code "56") (name "Net-(U8-PROG)") (class "Default")
      (node (ref "R6") (pin "2") (pinfunction "2_2") (pintype "input"))
      (node (ref "U8") (pin "2") (pinfunction "PROG_2") (pintype "unspecified"))
    )
    (net (code "57") (name "Net-(U8-TEMP)") (class "Default")
      (node (ref "R5") (pin "2") (pinfunction "2_2") (pintype "unspecified"))
      (node (ref "U8") (pin "1") (pinfunction "TEMP_1") (pintype "unspecified"))
    )
    (net (code "58") (name "Net-(U11-C1N)") (class "Default")
      (node (ref "C15") (pin "2") (pinfunction "2_2") (pintype "input"))
      (node (ref "U11") (pin "4") (pinfunction "C1N_4") (pintype "unspecified"))
    )
    (net (code "59") (name "Net-(U11-C1P)") (class "Default")
      (node (ref "C15") (pin "1") (pinfunction "1_1") (pintype "input"))
      (node (ref "U11") (pin "3") (pinfunction "C1P_3") (pintype "unspecified"))
    )
    (net (code "60") (name "Net-(U11-C2N)") (class "Default")
      (node (ref "C14") (pin "2") (pinfunction "2_2") (pintype "input"))
      (node (ref "U11") (pin "2") (pinfunction "C2N_2") (pintype "unspecified"))
    )
    (net (code "61") (name "Net-(U11-C2P)") (class "Default")
      (node (ref "C14") (pin "1") (pinfunction "1_1") (pintype "input"))
      (node (ref "U11") (pin "1") (pinfunction "C2P_1") (pintype "unspecified"))
    )
    (net (code "62") (name "Net-(U11-VCC)") (class "Default")
      (node (ref "C16") (pin "1") (pinfunction "1_1") (pintype "input"))
      (node (ref "U11") (pin "16") (pinfunction "VCC_16") (pintype "unspecified"))
    )
    (net (code "63") (name "Net-(U11-VCOMH)") (class "Default")
      (node (ref "C17") (pin "1") (pinfunction "1_1") (pintype "input"))
      (node (ref "U11") (pin "15") (pinfunction "VCOMH_15") (pintype "unspecified"))
    )
    (net (code "64") (name "Net-(U13-1IN-)") (class "Default")
      (node (ref "C23") (pin "2") (pinfunction "2_2") (pintype "input"))
      (node (ref "R16") (pin "1") (pinfunction "1_1") (pintype "input"))
      (node (ref "U13") (pin "2") (pinfunction "1IN-_2") (pintype "unspecified"))
    )
    (net (code "65") (name "Net-(U13-1OUT)") (class "Default")
      (node (ref "C24") (pin "2") (pinfunction "2_2") (pintype "input"))
      (node (ref "R16") (pin "2") (pinfunction "2_2") (pintype "input"))
      (node (ref "U13") (pin "1") (pinfunction "1OUT_1") (pintype "unspecified"))
    )
    (net (code "66") (name "Net-(U13-2IN-)") (class "Default")
      (node (ref "U13") (pin "6") (pinfunction "2IN-_6") (pintype "unspecified"))
      (node (ref "U13") (pin "7") (pinfunction "2OUT_7") (pintype "unspecified"))
    )
    (net (code "67") (name "OLED_CS#") (class "Default")
      (node (ref "U11") (pin "9") (pinfunction "CS_9") (pintype "unspecified"))
      (node (ref "U2") (pin "27") (pinfunction "IO16_27") (pintype "unspecified"))
    )
    (net (code "68") (name "RES#") (class "Default")
      (node (ref "U11") (pin "10") (pinfunction "RES_10") (pintype "unspecified"))
      (node (ref "U2") (pin "26") (pinfunction "IO4_26") (pintype "unspecified"))
    )
    (net (code "69") (name "SCK") (class "Default")
      (node (ref "CARD1") (pin "5") (pinfunction "CLX_5") (pintype "unspecified"))
      (node (ref "H1") (pin "3") (pinfunction "3_3") (pintype "input"))
      (node (ref "U11") (pin "12") (pinfunction "D0_12") (pintype "unspecified"))
      (node (ref "U2") (pin "30") (pinfunction "IO18_30") (pintype "unspecified"))
    )
    (net (code "70") (name "SD_CS#") (class "Default")
      (node (ref "CARD1") (pin "2") (pinfunction "CD/DAT3_2") (pintype "unspecified"))
      (node (ref "U2") (pin "28") (pinfunction "IO17_28") (pintype "unspecified"))
    )
    (net (code "71") (name "USB+") (class "Default")
      (node (ref "C4") (pin "1") (pinfunction "1_1") (pintype "input"))
      (node (ref "D1") (pin "1") (pinfunction "1_1") (pintype "unspecified"))
      (node (ref "SW2") (pin "3") (pinfunction "3_3") (pintype "unspecified"))
      (node (ref "U1") (pin "11") (pinfunction "VBUS_11") (pintype "unspecified"))
      (node (ref "U1") (pin "2") (pinfunction "VBUS_2") (pintype "unspecified"))
      (node (ref "U3") (pin "16") (pinfunction "VCC_16") (pintype "unspecified"))
    )
    (net (code "72") (name "VIN") (class "Default")
      (node (ref "C10") (pin "2") (pinfunction "2_2") (pintype "input"))
      (node (ref "C11") (pin "2") (pinfunction "2_2") (pintype "input"))
      (node (ref "C2") (pin "1") (pinfunction "1_1") (pintype "input"))
      (node (ref "D2") (pin "1") (pinfunction "C_1") (pintype "unspecified"))
      (node (ref "D3") (pin "1") (pinfunction "C_1") (pintype "unspecified"))
      (node (ref "D4") (pin "1") (pinfunction "C_1") (pintype "unspecified"))
      (node (ref "F1") (pin "2") (pinfunction "2_2") (pintype "input"))
      (node (ref "H1") (pin "12") (pinfunction "12_12") (pintype "input"))
      (node (ref "H2") (pin "1") (pinfunction "1_1") (pintype "input"))
      (node (ref "R7") (pin "1") (pinfunction "1_1") (pintype "input"))
      (node (ref "R8") (pin "1") (pinfunction "1_1") (pintype "input"))
      (node (ref "SW1") (pin "1") (pinfunction "1_1") (pintype "unspecified"))
      (node (ref "SW3") (pin "1") (pinfunction "1_1") (pintype "unspecified"))
      (node (ref "U12") (pin "1") (pinfunction "1_1") (pintype "input"))
      (node (ref "U6") (pin "1") (pinfunction "VIN_1") (pintype "input"))
      (node (ref "U8") (pin "4") (pinfunction "VCC_4") (pintype "unspecified"))
    )
    (net (code "73") (name "unconnected-(CARD1-DAT1-Pad8)") (class "Default")
      (node (ref "CARD1") (pin "8") (pinfunction "DAT1_8") (pintype "unspecified+no_connect"))
    )
    (net (code "74") (name "unconnected-(CARD1-DAT2-Pad1)") (class "Default")
      (node (ref "CARD1") (pin "1") (pinfunction "DAT2_1") (pintype "unspecified+no_connect"))
    )
    (net (code "75") (name "unconnected-(CARD1-PadCD)") (class "Default")
      (node (ref "CARD1") (pin "CD") (pinfunction "CD_CD") (pintype "unspecified+no_connect"))
    )
    (net (code "76") (name "unconnected-(U1-SBU1-Pad9)") (class "Default")
      (node (ref "U1") (pin "9") (pinfunction "SBU1_9") (pintype "unspecified+no_connect"))
    )
    (net (code "77") (name "unconnected-(U1-SBU2-Pad3)") (class "Default")
      (node (ref "U1") (pin "3") (pinfunction "SBU2_3") (pintype "unspecified+no_connect"))
    )
    (net (code "78") (name "unconnected-(U2-NC-Pad17)") (class "Default")
      (node (ref "U2") (pin "17") (pinfunction "NC_17") (pintype "unspecified+no_connect"))
    )
    (net (code "79") (name "unconnected-(U2-NC-Pad18)") (class "Default")
      (node (ref "U2") (pin "18") (pinfunction "NC_18") (pintype "unspecified+no_connect"))
    )
    (net (code "80") (name "unconnected-(U2-NC-Pad19)") (class "Default")
      (node (ref "U2") (pin "19") (pinfunction "NC_19") (pintype "unspecified+no_connect"))
    )
    (net (code "81") (name "unconnected-(U2-NC-Pad20)") (class "Default")
      (node (ref "U2") (pin "20") (pinfunction "NC_20") (pintype "unspecified+no_connect"))
    )
    (net (code "82") (name "unconnected-(U2-NC-Pad21)") (class "Default")
      (node (ref "U2") (pin "21") (pinfunction "NC_21") (pintype "unspecified+no_connect"))
    )
    (net (code "83") (name "unconnected-(U2-NC-Pad22)") (class "Default")
      (node (ref "U2") (pin "22") (pinfunction "NC_22") (pintype "unspecified+no_connect"))
    )
    (net (code "84") (name "unconnected-(U2-NC-Pad32)") (class "Default")
      (node (ref "U2") (pin "32") (pinfunction "NC_32") (pintype "unspecified+no_connect"))
    )
    (net (code "85") (name "unconnected-(U3-CTS#-Pad9)") (class "Default")
      (node (ref "U3") (pin "9") (pinfunction "CTS#_9") (pintype "unspecified+no_connect"))
    )
    (net (code "86") (name "unconnected-(U3-DCD#-Pad12)") (class "Default")
      (node (ref "U3") (pin "12") (pinfunction "DCD#_12") (pintype "unspecified+no_connect"))
    )
    (net (code "87") (name "unconnected-(U3-DSR#-Pad10)") (class "Default")
      (node (ref "U3") (pin "10") (pinfunction "DSR#_10") (pintype "unspecified+no_connect"))
    )
    (net (code "88") (name "unconnected-(U3-NC.-Pad7)") (class "Default")
      (node (ref "U3") (pin "7") (pinfunction "NC._7") (pintype "unspecified+no_connect"))
    )
    (net (code "89") (name "unconnected-(U3-OUT#-Pad8)") (class "Default")
      (node (ref "U3") (pin "8") (pinfunction "OUT#_8") (pintype "unspecified+no_connect"))
    )
    (net (code "90") (name "unconnected-(U3-R232-Pad15)") (class "Default")
      (node (ref "U3") (pin "15") (pinfunction "R232_15") (pintype "unspecified+no_connect"))
    )
    (net (code "91") (name "unconnected-(U3-RI#-Pad11)") (class "Default")
      (node (ref "U3") (pin "11") (pinfunction "RI#_11") (pintype "unspecified+no_connect"))
    )
  )
)
